# r.net
KiCad netlist of a schematic drawn in EAGLE
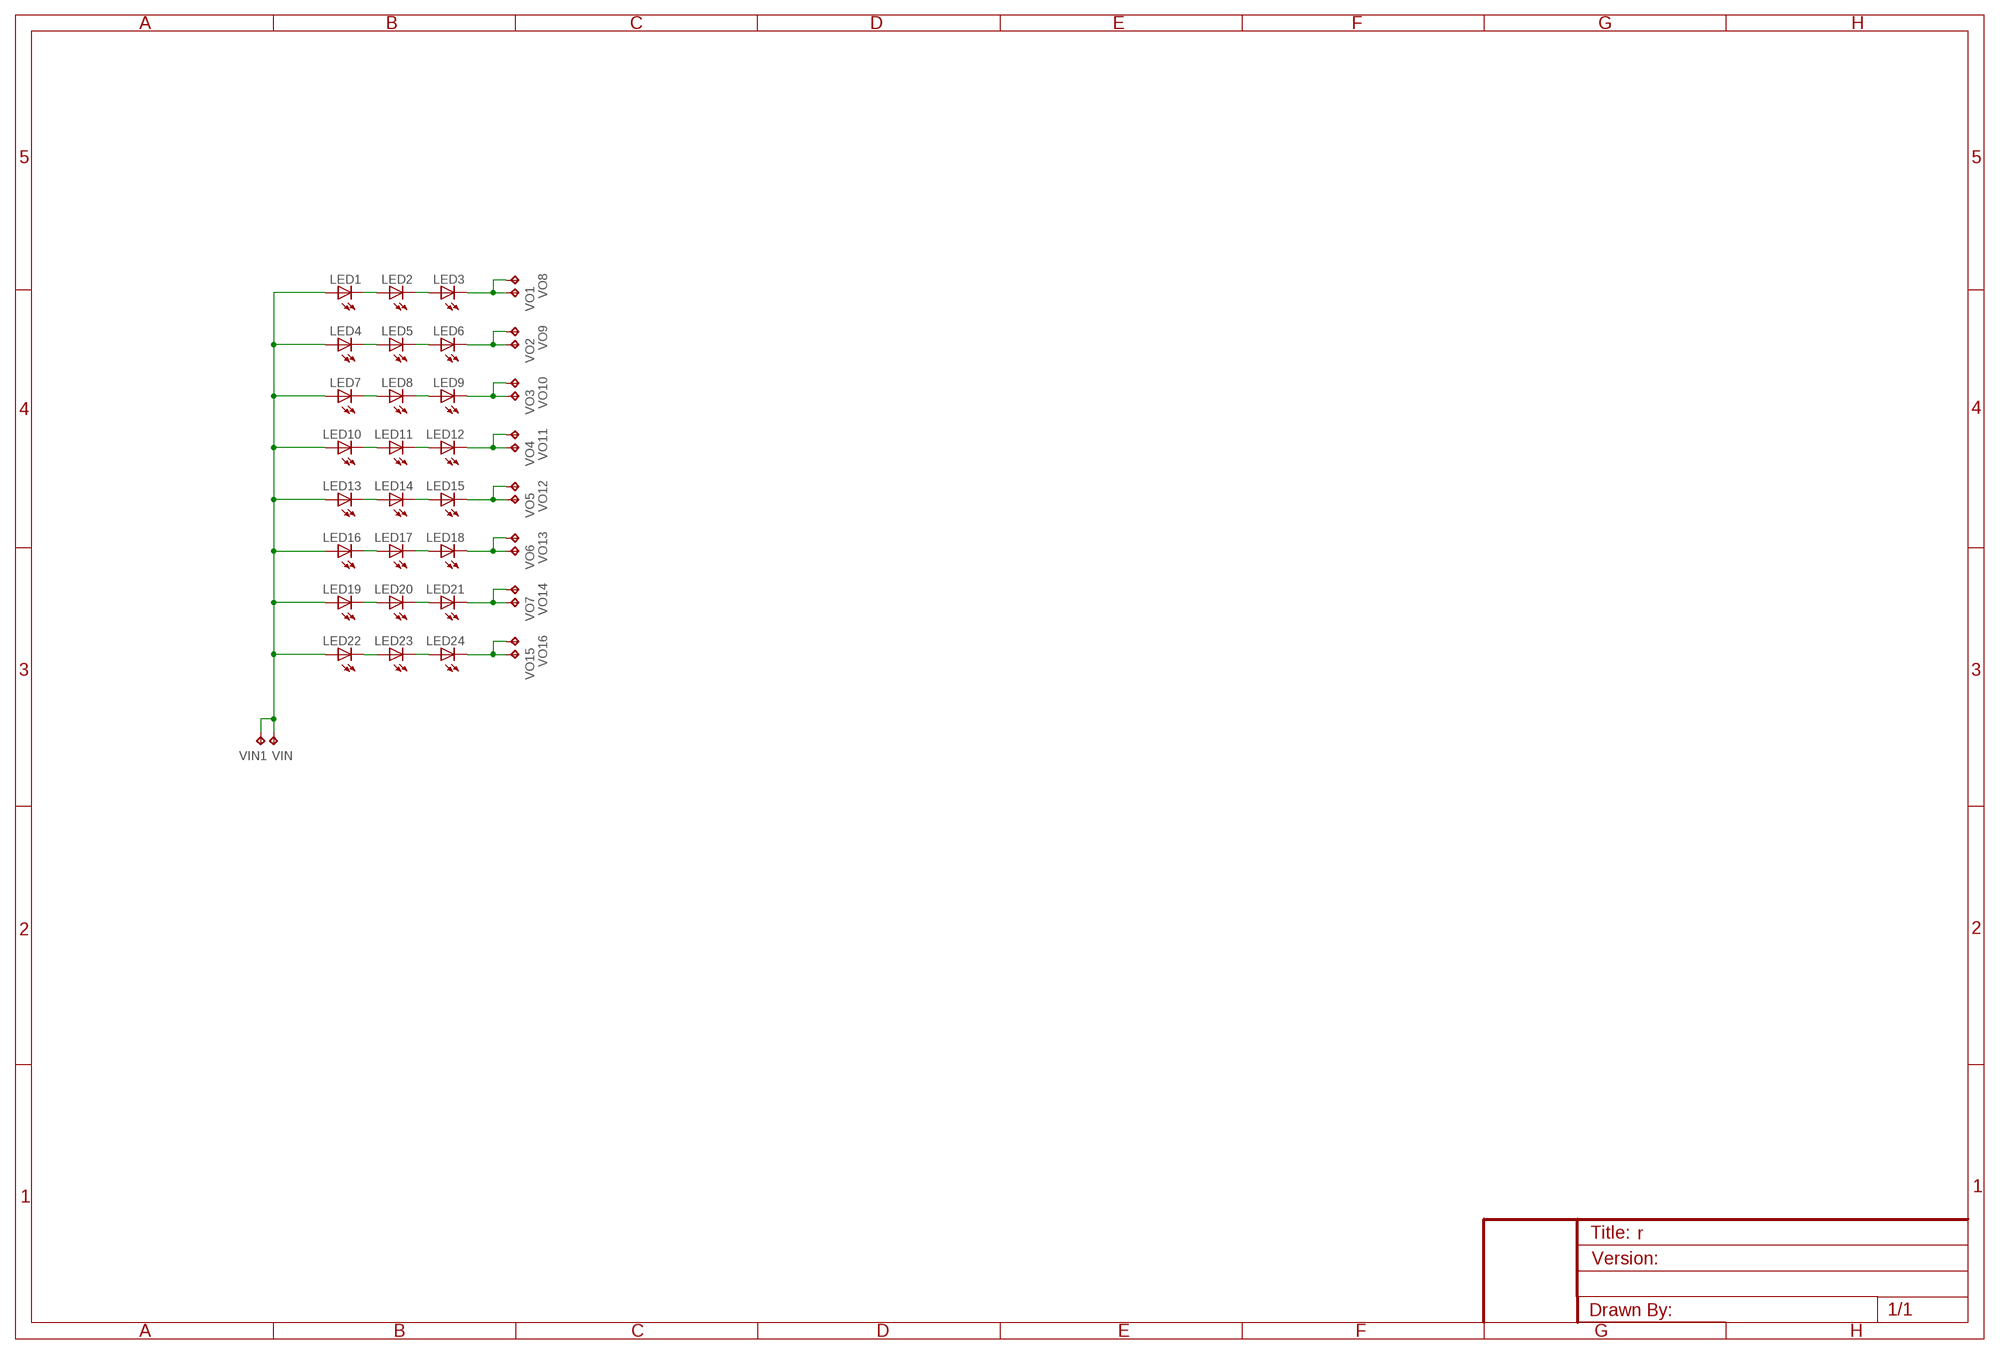
[diagram p0: schematic, sheet 1]

(export (version "E")
  (design (tool "Eeschema 10.0.6"))
  (components
    (comp (ref "LED1")
      (value "LED0805")
      (footprint "eagle-import:LED_0805")
      (libsource (lib "eagle-import") (part "LED0805"))
    )
    (comp (ref "LED2")
      (value "LED0805")
      (footprint "eagle-import:LED_0805")
      (libsource (lib "eagle-import") (part "LED0805"))
    )
    (comp (ref "LED3")
      (value "LED0805")
      (footprint "eagle-import:LED_0805")
      (libsource (lib "eagle-import") (part "LED0805"))
    )
    (comp (ref "LED4")
      (value "LED0805")
      (footprint "eagle-import:LED_0805")
      (libsource (lib "eagle-import") (part "LED0805"))
    )
    (comp (ref "LED5")
      (value "LED0805")
      (footprint "eagle-import:LED_0805")
      (libsource (lib "eagle-import") (part "LED0805"))
    )
    (comp (ref "LED6")
      (value "LED0805")
      (footprint "eagle-import:LED_0805")
      (libsource (lib "eagle-import") (part "LED0805"))
    )
    (comp (ref "LED7")
      (value "LED0805")
      (footprint "eagle-import:LED_0805")
      (libsource (lib "eagle-import") (part "LED0805"))
    )
    (comp (ref "LED8")
      (value "LED0805")
      (footprint "eagle-import:LED_0805")
      (libsource (lib "eagle-import") (part "LED0805"))
    )
    (comp (ref "LED9")
      (value "LED0805")
      (footprint "eagle-import:LED_0805")
      (libsource (lib "eagle-import") (part "LED0805"))
    )
    (comp (ref "LED10")
      (value "LED0805")
      (footprint "eagle-import:LED_0805")
      (libsource (lib "eagle-import") (part "LED0805"))
    )
    (comp (ref "LED11")
      (value "LED0805")
      (footprint "eagle-import:LED_0805")
      (libsource (lib "eagle-import") (part "LED0805"))
    )
    (comp (ref "LED12")
      (value "LED0805")
      (footprint "eagle-import:LED_0805")
      (libsource (lib "eagle-import") (part "LED0805"))
    )
    (comp (ref "LED13")
      (value "LED0805")
      (footprint "eagle-import:LED_0805")
      (libsource (lib "eagle-import") (part "LED0805"))
    )
    (comp (ref "LED14")
      (value "LED0805")
      (footprint "eagle-import:LED_0805")
      (libsource (lib "eagle-import") (part "LED0805"))
    )
    (comp (ref "LED15")
      (value "LED0805")
      (footprint "eagle-import:LED_0805")
      (libsource (lib "eagle-import") (part "LED0805"))
    )
    (comp (ref "LED16")
      (value "LED0805")
      (footprint "eagle-import:LED_0805")
      (libsource (lib "eagle-import") (part "LED0805"))
    )
    (comp (ref "LED17")
      (value "LED0805")
      (footprint "eagle-import:LED_0805")
      (libsource (lib "eagle-import") (part "LED0805"))
    )
    (comp (ref "LED18")
      (value "LED0805")
      (footprint "eagle-import:LED_0805")
      (libsource (lib "eagle-import") (part "LED0805"))
    )
    (comp (ref "LED19")
      (value "LED0805")
      (footprint "eagle-import:LED_0805")
      (libsource (lib "eagle-import") (part "LED0805"))
    )
    (comp (ref "LED20")
      (value "LED0805")
      (footprint "eagle-import:LED_0805")
      (libsource (lib "eagle-import") (part "LED0805"))
    )
    (comp (ref "LED21")
      (value "LED0805")
      (footprint "eagle-import:LED_0805")
      (libsource (lib "eagle-import") (part "LED0805"))
    )
    (comp (ref "LED22")
      (value "LED0805")
      (footprint "eagle-import:LED_0805")
      (libsource (lib "eagle-import") (part "LED0805"))
    )
    (comp (ref "LED23")
      (value "LED0805")
      (footprint "eagle-import:LED_0805")
      (libsource (lib "eagle-import") (part "LED0805"))
    )
    (comp (ref "LED24")
      (value "LED0805")
      (footprint "eagle-import:LED_0805")
      (libsource (lib "eagle-import") (part "LED0805"))
    )
    (comp (ref "VIN")
      (value "TEST_POINTPAD1-20")
      (footprint "eagle-import:P1-20")
      (libsource (lib "eagle-import") (part "TEST_POINTPAD1-20"))
    )
    (comp (ref "VIN1")
      (value "TEST_POINTPAD1-20")
      (footprint "eagle-import:P1-20")
      (libsource (lib "eagle-import") (part "TEST_POINTPAD1-20"))
    )
    (comp (ref "VO1")
      (value "TEST_POINTPAD1-20")
      (footprint "eagle-import:P1-20")
      (libsource (lib "eagle-import") (part "TEST_POINTPAD1-20"))
    )
    (comp (ref "VO2")
      (value "TEST_POINTPAD1-20")
      (footprint "eagle-import:P1-20")
      (libsource (lib "eagle-import") (part "TEST_POINTPAD1-20"))
    )
    (comp (ref "VO3")
      (value "TEST_POINTPAD1-20")
      (footprint "eagle-import:P1-20")
      (libsource (lib "eagle-import") (part "TEST_POINTPAD1-20"))
    )
    (comp (ref "VO4")
      (value "TEST_POINTPAD1-20")
      (footprint "eagle-import:P1-20")
      (libsource (lib "eagle-import") (part "TEST_POINTPAD1-20"))
    )
    (comp (ref "VO5")
      (value "TEST_POINTPAD1-20")
      (footprint "eagle-import:P1-20")
      (libsource (lib "eagle-import") (part "TEST_POINTPAD1-20"))
    )
    (comp (ref "VO6")
      (value "TEST_POINTPAD1-20")
      (footprint "eagle-import:P1-20")
      (libsource (lib "eagle-import") (part "TEST_POINTPAD1-20"))
    )
    (comp (ref "VO7")
      (value "TEST_POINTPAD1-20")
      (footprint "eagle-import:P1-20")
      (libsource (lib "eagle-import") (part "TEST_POINTPAD1-20"))
    )
    (comp (ref "VO8")
      (value "TEST_POINTPAD1-20")
      (footprint "eagle-import:P1-20")
      (libsource (lib "eagle-import") (part "TEST_POINTPAD1-20"))
    )
    (comp (ref "VO9")
      (value "TEST_POINTPAD1-20")
      (footprint "eagle-import:P1-20")
      (libsource (lib "eagle-import") (part "TEST_POINTPAD1-20"))
    )
    (comp (ref "VO10")
      (value "TEST_POINTPAD1-20")
      (footprint "eagle-import:P1-20")
      (libsource (lib "eagle-import") (part "TEST_POINTPAD1-20"))
    )
    (comp (ref "VO11")
      (value "TEST_POINTPAD1-20")
      (footprint "eagle-import:P1-20")
      (libsource (lib "eagle-import") (part "TEST_POINTPAD1-20"))
    )
    (comp (ref "VO12")
      (value "TEST_POINTPAD1-20")
      (footprint "eagle-import:P1-20")
      (libsource (lib "eagle-import") (part "TEST_POINTPAD1-20"))
    )
    (comp (ref "VO13")
      (value "TEST_POINTPAD1-20")
      (footprint "eagle-import:P1-20")
      (libsource (lib "eagle-import") (part "TEST_POINTPAD1-20"))
    )
    (comp (ref "VO14")
      (value "TEST_POINTPAD1-20")
      (footprint "eagle-import:P1-20")
      (libsource (lib "eagle-import") (part "TEST_POINTPAD1-20"))
    )
    (comp (ref "VO15")
      (value "TEST_POINTPAD1-20")
      (footprint "eagle-import:P1-20")
      (libsource (lib "eagle-import") (part "TEST_POINTPAD1-20"))
    )
    (comp (ref "VO16")
      (value "TEST_POINTPAD1-20")
      (footprint "eagle-import:P1-20")
      (libsource (lib "eagle-import") (part "TEST_POINTPAD1-20"))
    )
  )
  (nets
    (net (code "1") (name "Net-(LED1-PadA)") (class "Default")
      (node (ref "LED1") (pin "A") (pinfunction "A_A") (pintype "passive"))
      (node (ref "LED10") (pin "A") (pinfunction "A_A") (pintype "passive"))
      (node (ref "LED13") (pin "A") (pinfunction "A_A") (pintype "passive"))
      (node (ref "LED16") (pin "A") (pinfunction "A_A") (pintype "passive"))
      (node (ref "LED19") (pin "A") (pinfunction "A_A") (pintype "passive"))
      (node (ref "LED22") (pin "A") (pinfunction "A_A") (pintype "passive"))
      (node (ref "LED4") (pin "A") (pinfunction "A_A") (pintype "passive"))
      (node (ref "LED7") (pin "A") (pinfunction "A_A") (pintype "passive"))
      (node (ref "VIN") (pin "TP") (pinfunction "TP_TP") (pintype "input"))
      (node (ref "VIN1") (pin "TP") (pinfunction "TP_TP") (pintype "input"))
    )
    (net (code "2") (name "Net-(LED1-PadC)") (class "Default")
      (node (ref "LED1") (pin "C") (pinfunction "C_C") (pintype "passive"))
      (node (ref "LED2") (pin "A") (pinfunction "A_A") (pintype "passive"))
    )
    (net (code "3") (name "Net-(LED2-PadC)") (class "Default")
      (node (ref "LED2") (pin "C") (pinfunction "C_C") (pintype "passive"))
      (node (ref "LED3") (pin "A") (pinfunction "A_A") (pintype "passive"))
    )
    (net (code "4") (name "Net-(LED3-PadC)") (class "Default")
      (node (ref "LED3") (pin "C") (pinfunction "C_C") (pintype "passive"))
      (node (ref "VO1") (pin "TP") (pinfunction "TP_TP") (pintype "input"))
      (node (ref "VO8") (pin "TP") (pinfunction "TP_TP") (pintype "input"))
    )
    (net (code "5") (name "Net-(LED4-PadC)") (class "Default")
      (node (ref "LED4") (pin "C") (pinfunction "C_C") (pintype "passive"))
      (node (ref "LED5") (pin "A") (pinfunction "A_A") (pintype "passive"))
    )
    (net (code "6") (name "Net-(LED5-PadC)") (class "Default")
      (node (ref "LED5") (pin "C") (pinfunction "C_C") (pintype "passive"))
      (node (ref "LED6") (pin "A") (pinfunction "A_A") (pintype "passive"))
    )
    (net (code "7") (name "Net-(LED6-PadC)") (class "Default")
      (node (ref "LED6") (pin "C") (pinfunction "C_C") (pintype "passive"))
      (node (ref "VO2") (pin "TP") (pinfunction "TP_TP") (pintype "input"))
      (node (ref "VO9") (pin "TP") (pinfunction "TP_TP") (pintype "input"))
    )
    (net (code "8") (name "Net-(LED7-PadC)") (class "Default")
      (node (ref "LED7") (pin "C") (pinfunction "C_C") (pintype "passive"))
      (node (ref "LED8") (pin "A") (pinfunction "A_A") (pintype "passive"))
    )
    (net (code "9") (name "Net-(LED8-PadC)") (class "Default")
      (node (ref "LED8") (pin "C") (pinfunction "C_C") (pintype "passive"))
      (node (ref "LED9") (pin "A") (pinfunction "A_A") (pintype "passive"))
    )
    (net (code "10") (name "Net-(LED9-PadC)") (class "Default")
      (node (ref "LED9") (pin "C") (pinfunction "C_C") (pintype "passive"))
      (node (ref "VO10") (pin "TP") (pinfunction "TP_TP") (pintype "input"))
      (node (ref "VO3") (pin "TP") (pinfunction "TP_TP") (pintype "input"))
    )
    (net (code "11") (name "Net-(LED10-PadC)") (class "Default")
      (node (ref "LED10") (pin "C") (pinfunction "C_C") (pintype "passive"))
      (node (ref "LED11") (pin "A") (pinfunction "A_A") (pintype "passive"))
    )
    (net (code "12") (name "Net-(LED11-PadC)") (class "Default")
      (node (ref "LED11") (pin "C") (pinfunction "C_C") (pintype "passive"))
      (node (ref "LED12") (pin "A") (pinfunction "A_A") (pintype "passive"))
    )
    (net (code "13") (name "Net-(LED12-PadC)") (class "Default")
      (node (ref "LED12") (pin "C") (pinfunction "C_C") (pintype "passive"))
      (node (ref "VO11") (pin "TP") (pinfunction "TP_TP") (pintype "input"))
      (node (ref "VO4") (pin "TP") (pinfunction "TP_TP") (pintype "input"))
    )
    (net (code "14") (name "Net-(LED13-PadC)") (class "Default")
      (node (ref "LED13") (pin "C") (pinfunction "C_C") (pintype "passive"))
      (node (ref "LED14") (pin "A") (pinfunction "A_A") (pintype "passive"))
    )
    (net (code "15") (name "Net-(LED14-PadC)") (class "Default")
      (node (ref "LED14") (pin "C") (pinfunction "C_C") (pintype "passive"))
      (node (ref "LED15") (pin "A") (pinfunction "A_A") (pintype "passive"))
    )
    (net (code "16") (name "Net-(LED15-PadC)") (class "Default")
      (node (ref "LED15") (pin "C") (pinfunction "C_C") (pintype "passive"))
      (node (ref "VO12") (pin "TP") (pinfunction "TP_TP") (pintype "input"))
      (node (ref "VO5") (pin "TP") (pinfunction "TP_TP") (pintype "input"))
    )
    (net (code "17") (name "Net-(LED16-PadC)") (class "Default")
      (node (ref "LED16") (pin "C") (pinfunction "C_C") (pintype "passive"))
      (node (ref "LED17") (pin "A") (pinfunction "A_A") (pintype "passive"))
    )
    (net (code "18") (name "Net-(LED17-PadC)") (class "Default")
      (node (ref "LED17") (pin "C") (pinfunction "C_C") (pintype "passive"))
      (node (ref "LED18") (pin "A") (pinfunction "A_A") (pintype "passive"))
    )
    (net (code "19") (name "Net-(LED18-PadC)") (class "Default")
      (node (ref "LED18") (pin "C") (pinfunction "C_C") (pintype "passive"))
      (node (ref "VO13") (pin "TP") (pinfunction "TP_TP") (pintype "input"))
      (node (ref "VO6") (pin "TP") (pinfunction "TP_TP") (pintype "input"))
    )
    (net (code "20") (name "Net-(LED19-PadC)") (class "Default")
      (node (ref "LED19") (pin "C") (pinfunction "C_C") (pintype "passive"))
      (node (ref "LED20") (pin "A") (pinfunction "A_A") (pintype "passive"))
    )
    (net (code "21") (name "Net-(LED20-PadC)") (class "Default")
      (node (ref "LED20") (pin "C") (pinfunction "C_C") (pintype "passive"))
      (node (ref "LED21") (pin "A") (pinfunction "A_A") (pintype "passive"))
    )
    (net (code "22") (name "Net-(LED21-PadC)") (class "Default")
      (node (ref "LED21") (pin "C") (pinfunction "C_C") (pintype "passive"))
      (node (ref "VO14") (pin "TP") (pinfunction "TP_TP") (pintype "input"))
      (node (ref "VO7") (pin "TP") (pinfunction "TP_TP") (pintype "input"))
    )
    (net (code "23") (name "Net-(LED22-PadC)") (class "Default")
      (node (ref "LED22") (pin "C") (pinfunction "C_C") (pintype "passive"))
      (node (ref "LED23") (pin "A") (pinfunction "A_A") (pintype "passive"))
    )
    (net (code "24") (name "Net-(LED23-PadC)") (class "Default")
      (node (ref "LED23") (pin "C") (pinfunction "C_C") (pintype "passive"))
      (node (ref "LED24") (pin "A") (pinfunction "A_A") (pintype "passive"))
    )
    (net (code "25") (name "Net-(LED24-PadC)") (class "Default")
      (node (ref "LED24") (pin "C") (pinfunction "C_C") (pintype "passive"))
      (node (ref "VO15") (pin "TP") (pinfunction "TP_TP") (pintype "input"))
      (node (ref "VO16") (pin "TP") (pinfunction "TP_TP") (pintype "input"))
    )
  )
)
